# Bridge_DS2482.net
KiCad netlist of a schematic drawn in EAGLE
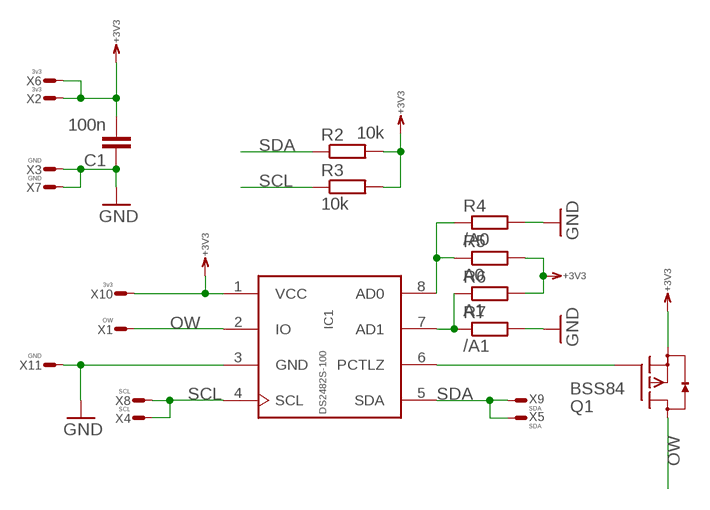
[diagram p0: schematic, sheet 1]

(export (version "E")
  (design (tool "Eeschema 10.0.6"))
  (components
    (comp (ref "C1")
      (value "100n")
      (footprint "eagle-import:0603")
      (libsource (lib "eagle-import") (part "C0603"))
    )
    (comp (ref "IC1")
      (value "DS2482S-100")
      (footprint "eagle-import:SO8")
      (libsource (lib "eagle-import") (part "DS2482S"))
    )
    (comp (ref "Q1")
      (value "BSS84")
      (footprint "eagle-import:SOT23")
      (libsource (lib "eagle-import") (part "FET-PDSOT23"))
    )
    (comp (ref "R2")
      (value "10k")
      (footprint "eagle-import:0603")
      (libsource (lib "eagle-import") (part "R0603"))
    )
    (comp (ref "R3")
      (value "10k")
      (footprint "eagle-import:0603")
      (libsource (lib "eagle-import") (part "R0603"))
    )
    (comp (ref "R4")
      (value "/A0")
      (footprint "eagle-import:0603")
      (libsource (lib "eagle-import") (part "R0603"))
    )
    (comp (ref "R5")
      (value "A0")
      (footprint "eagle-import:0603")
      (libsource (lib "eagle-import") (part "R0603"))
    )
    (comp (ref "R6")
      (value "A1")
      (footprint "eagle-import:0603")
      (libsource (lib "eagle-import") (part "R0603"))
    )
    (comp (ref "R7")
      (value "/A1")
      (footprint "eagle-import:0603")
      (libsource (lib "eagle-import") (part "R0603"))
    )
    (comp (ref "X1")
      (value "OW")
      (footprint "eagle-import:T1.6_0.9")
      (libsource (lib "eagle-import") (part "WIREPADT1.6/0.9"))
    )
    (comp (ref "X2")
      (value "3v3")
      (footprint "eagle-import:T1.6_0.9")
      (libsource (lib "eagle-import") (part "WIREPADT1.6/0.9"))
    )
    (comp (ref "X3")
      (value "GND")
      (footprint "eagle-import:T1.6_0.9")
      (libsource (lib "eagle-import") (part "WIREPADT1.6/0.9"))
    )
    (comp (ref "X4")
      (value "SCL")
      (footprint "eagle-import:T1.6_0.9")
      (libsource (lib "eagle-import") (part "WIREPADT1.6/0.9"))
    )
    (comp (ref "X5")
      (value "SDA")
      (footprint "eagle-import:T1.6_0.9")
      (libsource (lib "eagle-import") (part "WIREPADT1.6/0.9"))
    )
    (comp (ref "X6")
      (value "3v3")
      (footprint "eagle-import:T1.6_0.9")
      (libsource (lib "eagle-import") (part "WIREPADT1.6/0.9"))
    )
    (comp (ref "X7")
      (value "GND")
      (footprint "eagle-import:T1.6_0.9")
      (libsource (lib "eagle-import") (part "WIREPADT1.6/0.9"))
    )
    (comp (ref "X8")
      (value "SCL")
      (footprint "eagle-import:T1.6_0.9")
      (libsource (lib "eagle-import") (part "WIREPADT1.6/0.9"))
    )
    (comp (ref "X9")
      (value "SDA")
      (footprint "eagle-import:T1.6_0.9")
      (libsource (lib "eagle-import") (part "WIREPADT1.6/0.9"))
    )
    (comp (ref "X10")
      (value "3v3")
      (footprint "eagle-import:T1.6_0.9")
      (libsource (lib "eagle-import") (part "WIREPADT1.6/0.9"))
    )
    (comp (ref "X11")
      (value "GND")
      (footprint "eagle-import:T1.6_0.9")
      (libsource (lib "eagle-import") (part "WIREPADT1.6/0.9"))
    )
  )
  (nets
    (net (code "1") (name "+3V3") (class "Default")
      (node (ref "C1") (pin "2") (pinfunction "2_2") (pintype "passive"))
      (node (ref "IC1") (pin "1") (pinfunction "VCC_1") (pintype "bidirectional"))
      (node (ref "Q1") (pin "2") (pinfunction "S_2") (pintype "passive"))
      (node (ref "R2") (pin "2") (pinfunction "2_2") (pintype "passive"))
      (node (ref "R3") (pin "2") (pinfunction "2_2") (pintype "passive"))
      (node (ref "R5") (pin "2") (pinfunction "2_2") (pintype "passive"))
      (node (ref "R6") (pin "2") (pinfunction "2_2") (pintype "passive"))
      (node (ref "X10") (pin "1") (pinfunction "S_1") (pintype "passive"))
      (node (ref "X2") (pin "1") (pinfunction "S_1") (pintype "passive"))
      (node (ref "X6") (pin "1") (pinfunction "S_1") (pintype "passive"))
    )
    (net (code "2") (name "/OW") (class "Default")
      (node (ref "IC1") (pin "2") (pinfunction "IO_2") (pintype "bidirectional"))
      (node (ref "Q1") (pin "3") (pinfunction "D_3") (pintype "passive"))
      (node (ref "X1") (pin "1") (pinfunction "S_1") (pintype "passive"))
    )
    (net (code "3") (name "/SCL") (class "Default")
      (node (ref "IC1") (pin "4") (pinfunction "SCL_4") (pintype "bidirectional"))
      (node (ref "R3") (pin "1") (pinfunction "1_1") (pintype "passive"))
      (node (ref "X4") (pin "1") (pinfunction "S_1") (pintype "passive"))
      (node (ref "X8") (pin "1") (pinfunction "S_1") (pintype "passive"))
    )
    (net (code "4") (name "/SDA") (class "Default")
      (node (ref "IC1") (pin "5") (pinfunction "SDA_5") (pintype "bidirectional"))
      (node (ref "R2") (pin "1") (pinfunction "1_1") (pintype "passive"))
      (node (ref "X5") (pin "1") (pinfunction "S_1") (pintype "passive"))
      (node (ref "X9") (pin "1") (pinfunction "S_1") (pintype "passive"))
    )
    (net (code "5") (name "GND") (class "Default")
      (node (ref "C1") (pin "1") (pinfunction "1_1") (pintype "passive"))
      (node (ref "IC1") (pin "3") (pinfunction "GND_3") (pintype "bidirectional"))
      (node (ref "R4") (pin "2") (pinfunction "2_2") (pintype "passive"))
      (node (ref "R7") (pin "2") (pinfunction "2_2") (pintype "passive"))
      (node (ref "X11") (pin "1") (pinfunction "S_1") (pintype "passive"))
      (node (ref "X3") (pin "1") (pinfunction "S_1") (pintype "passive"))
      (node (ref "X7") (pin "1") (pinfunction "S_1") (pintype "passive"))
    )
    (net (code "6") (name "Net-(IC1-AD0)") (class "Default")
      (node (ref "IC1") (pin "8") (pinfunction "AD0_8") (pintype "input"))
      (node (ref "R4") (pin "1") (pinfunction "1_1") (pintype "passive"))
      (node (ref "R5") (pin "1") (pinfunction "1_1") (pintype "passive"))
    )
    (net (code "7") (name "Net-(IC1-AD1)") (class "Default")
      (node (ref "IC1") (pin "7") (pinfunction "AD1_7") (pintype "input"))
      (node (ref "R6") (pin "1") (pinfunction "1_1") (pintype "passive"))
      (node (ref "R7") (pin "1") (pinfunction "1_1") (pintype "passive"))
    )
    (net (code "8") (name "Net-(IC1-PCTLZ)") (class "Default")
      (node (ref "IC1") (pin "6") (pinfunction "PCTLZ_6") (pintype "output"))
      (node (ref "Q1") (pin "1") (pinfunction "G_1") (pintype "passive"))
    )
  )
)
